# Power_-_5V0.net
KiCad netlist of a schematic drawn in Altium Designer
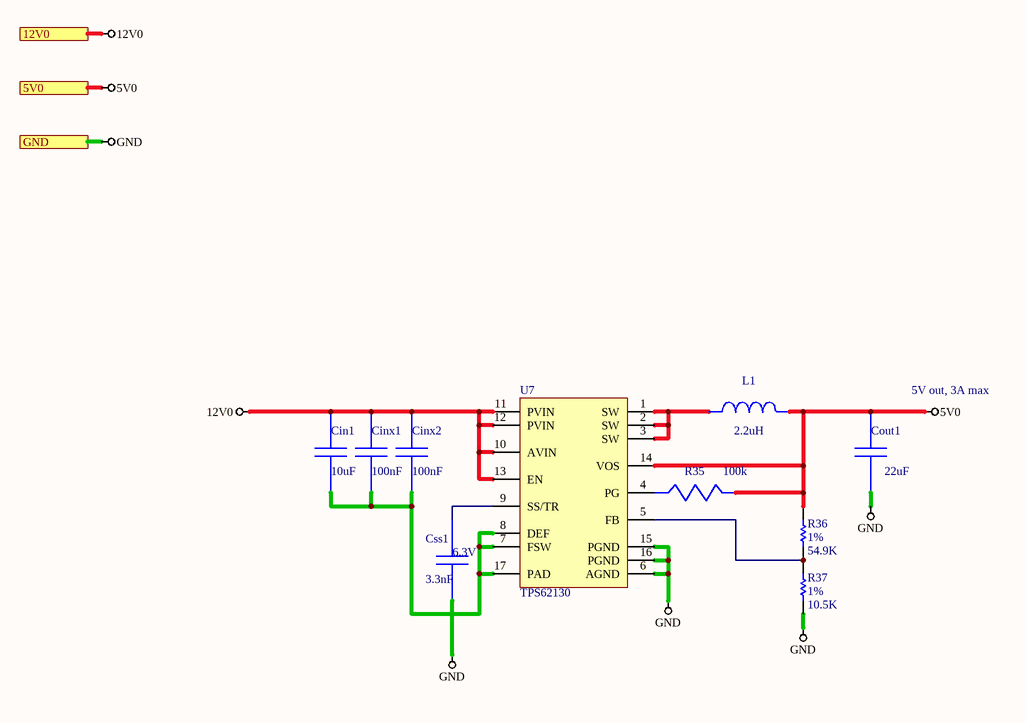
[diagram p0: Power - 5V0.SchDoc]

(export (version "E")
  (design (tool "Eeschema 10.0.6"))
  (components
    (comp (ref "Cin1")
      (value "10uF")
      (footprint "1206")
      (description "GRM31CR61E106KA1")
      (fields (field (name "MANUFACTURER PART NUMBER") "GRM31CR61E106KA12L"))
      (libsource (lib "TI WEBENCH") (part "Cin"))
    )
    (comp (ref "Cinx1")
      (value "100nF")
      (footprint "C-0603")
      (description "C0603C104K3RACTU")
      (libsource (lib "TI WEBENCH") (part "Cinx"))
    )
    (comp (ref "Cinx2")
      (value "100nF")
      (footprint "C-0603")
      (description "C0603C104K3RACTU")
      (libsource (lib "TI WEBENCH") (part "Cinx"))
    )
    (comp (ref "Cout1")
      (value "22uF")
      (footprint "C-0805")
      (description "LMK212BJ226MG-T")
      (libsource (lib "TI WEBENCH") (part "Cout"))
    )
    (comp (ref "Css1")
      (value "6.3V")
      (footprint "CAPC0402(1005)60_L")
      (description "GRM022R60J332KE19D")
      (fields (field (name "ALTIUM_VALUE") "3.3nF"))
      (libsource (lib "TI WEBENCH") (part "Css"))
    )
    (comp (ref "L1")
      (value "2.2uH")
      (footprint "XAL4020")
      (description "XAL4020-222MEB")
      (libsource (lib "TI WEBENCH") (part "L1"))
    )
    (comp (ref "R35")
      (value "100k")
      (footprint "CAPC0402(1005)60_L")
      (description "CRCW0402100KFKED")
      (libsource (lib "TI WEBENCH") (part "Rpg"))
    )
    (comp (ref "R36")
      (value "1%")
      (footprint "RESC0402(1005)40_L")
      (description "Resistor")
      (fields (field (name "ALTIUM_VALUE") "54.9K") (field (name "PUBLISHER") "Altium Limited"))
      (libsource (lib "Miscellaneous Devices") (part "Res1"))
    )
    (comp (ref "R37")
      (value "1%")
      (footprint "RESC0402(1005)40_L")
      (description "Resistor")
      (fields (field (name "ALTIUM_VALUE") "10.5K") (field (name "PUBLISHER") "Altium Limited"))
      (libsource (lib "Miscellaneous Devices") (part "Res1"))
    )
    (comp (ref "U7") (value "TPS62130") (footprint "S-PVQFN-N16") (libsource (lib "Power") (part "TPS6213X")))
  )
  (nets
    (net (code "1") (name "5V0") (class "Default")
      (node (ref "Cout1") (pin "1") (pinfunction "1_1") (pintype "passive"))
      (node (ref "L1") (pin "2") (pinfunction "2_2") (pintype "passive"))
      (node (ref "R35") (pin "1") (pinfunction "1_1") (pintype "passive"))
      (node (ref "R36") (pin "2") (pinfunction "2_2") (pintype "passive"))
      (node (ref "U7") (pin "14") (pinfunction "VOS_14") (pintype "passive"))
    )
    (net (code "2") (name "12V0") (class "Default")
      (node (ref "Cin1") (pin "1") (pinfunction "1_1") (pintype "passive"))
      (node (ref "Cinx1") (pin "1") (pinfunction "1_1") (pintype "passive"))
      (node (ref "Cinx2") (pin "1") (pinfunction "1_1") (pintype "passive"))
      (node (ref "U7") (pin "10") (pinfunction "AVIN_10") (pintype "passive"))
      (node (ref "U7") (pin "11") (pinfunction "PVIN_11") (pintype "passive"))
      (node (ref "U7") (pin "12") (pinfunction "PVIN_12") (pintype "passive"))
      (node (ref "U7") (pin "13") (pinfunction "EN_13") (pintype "passive"))
    )
    (net (code "3") (name "GND") (class "Default")
      (node (ref "Cout1") (pin "2") (pinfunction "2_2") (pintype "passive"))
      (node (ref "Css1") (pin "2") (pinfunction "2_2") (pintype "passive"))
      (node (ref "R37") (pin "1") (pinfunction "1_1") (pintype "passive"))
      (node (ref "U7") (pin "15") (pinfunction "PGND_15") (pintype "passive"))
      (node (ref "U7") (pin "16") (pinfunction "PGND_16") (pintype "passive"))
      (node (ref "U7") (pin "6") (pinfunction "AGND_6") (pintype "passive"))
    )
    (net (code "4") (name "Net-(L1-Pad1)") (class "Default")
      (node (ref "L1") (pin "1") (pinfunction "1_1") (pintype "passive"))
      (node (ref "U7") (pin "1") (pinfunction "SW_1") (pintype "passive"))
      (node (ref "U7") (pin "2") (pinfunction "SW_2") (pintype "passive"))
      (node (ref "U7") (pin "3") (pinfunction "SW_3") (pintype "passive"))
    )
    (net (code "5") (name "Net-(U7-DEF)") (class "Default")
      (node (ref "Cin1") (pin "2") (pinfunction "2_2") (pintype "passive"))
      (node (ref "Cinx1") (pin "2") (pinfunction "2_2") (pintype "passive"))
      (node (ref "Cinx2") (pin "2") (pinfunction "2_2") (pintype "passive"))
      (node (ref "U7") (pin "17") (pinfunction "PAD_17") (pintype "passive"))
      (node (ref "U7") (pin "7") (pinfunction "FSW_7") (pintype "passive"))
      (node (ref "U7") (pin "8") (pinfunction "DEF_8") (pintype "passive"))
    )
    (net (code "6") (name "Net-(U7-FB)") (class "Default")
      (node (ref "R36") (pin "1") (pinfunction "1_1") (pintype "passive"))
      (node (ref "R37") (pin "2") (pinfunction "2_2") (pintype "passive"))
      (node (ref "U7") (pin "5") (pinfunction "FB_5") (pintype "passive"))
    )
    (net (code "7") (name "Net-(U7-PG)") (class "Default")
      (node (ref "R35") (pin "2") (pinfunction "2_2") (pintype "passive"))
      (node (ref "U7") (pin "4") (pinfunction "PG_4") (pintype "passive"))
    )
    (net (code "8") (name "Net-(U7-SS{slash}TR)") (class "Default")
      (node (ref "Css1") (pin "1") (pinfunction "1_1") (pintype "passive"))
      (node (ref "U7") (pin "9") (pinfunction "SS/TR_9") (pintype "passive"))
    )
  )
)
